# Expansion.net
KiCad netlist of a schematic drawn in Altium Designer
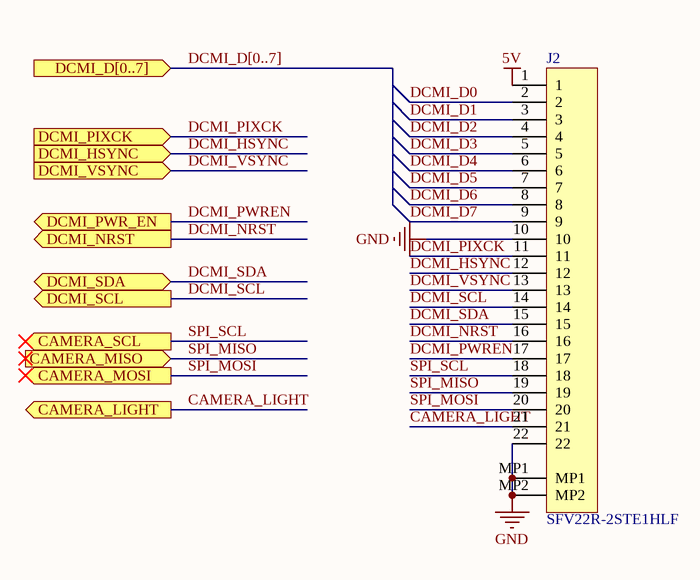
[diagram p0: Expansion.SchDoc]

(export (version "E")
  (design (tool "Eeschema 10.0.6"))
  (components
    (comp (ref "J2")
      (value "SFV22R-2STE1HLF")
      (footprint "fpc-22")
      (description "Connector")
      (fields (field (name "MANUFACTURER") "Amphenol FCI"))
      (libsource (lib "yildizIoT Library") (part "FPC-22"))
    )
  )
  (nets
    (net (code "1") (name "/CAMERA_LIGHT") (class "Default")
      (node (ref "J2") (pin "21") (pinfunction "21_21") (pintype "passive"))
    )
    (net (code "2") (name "/DCMI_D0") (class "Default")
      (node (ref "J2") (pin "2") (pinfunction "2_2") (pintype "passive"))
    )
    (net (code "3") (name "/DCMI_D1") (class "Default")
      (node (ref "J2") (pin "3") (pinfunction "3_3") (pintype "passive"))
    )
    (net (code "4") (name "/DCMI_D2") (class "Default")
      (node (ref "J2") (pin "4") (pinfunction "4_4") (pintype "passive"))
    )
    (net (code "5") (name "/DCMI_D3") (class "Default")
      (node (ref "J2") (pin "5") (pinfunction "5_5") (pintype "passive"))
    )
    (net (code "6") (name "/DCMI_D4") (class "Default")
      (node (ref "J2") (pin "6") (pinfunction "6_6") (pintype "passive"))
    )
    (net (code "7") (name "/DCMI_D5") (class "Default")
      (node (ref "J2") (pin "7") (pinfunction "7_7") (pintype "passive"))
    )
    (net (code "8") (name "/DCMI_D6") (class "Default")
      (node (ref "J2") (pin "8") (pinfunction "8_8") (pintype "passive"))
    )
    (net (code "9") (name "/DCMI_D7") (class "Default")
      (node (ref "J2") (pin "9") (pinfunction "9_9") (pintype "passive"))
    )
    (net (code "11") (name "/DCMI_HSYNC") (class "Default")
      (node (ref "J2") (pin "12") (pinfunction "12_12") (pintype "passive"))
    )
    (net (code "12") (name "/DCMI_NRST") (class "Default")
      (node (ref "J2") (pin "16") (pinfunction "16_16") (pintype "passive"))
    )
    (net (code "13") (name "/DCMI_PIXCK") (class "Default")
      (node (ref "J2") (pin "11") (pinfunction "11_11") (pintype "passive"))
    )
    (net (code "14") (name "/DCMI_PWREN") (class "Default")
      (node (ref "J2") (pin "17") (pinfunction "17_17") (pintype "passive"))
    )
    (net (code "15") (name "/DCMI_SCL") (class "Default")
      (node (ref "J2") (pin "14") (pinfunction "14_14") (pintype "passive"))
    )
    (net (code "16") (name "/DCMI_SDA") (class "Default")
      (node (ref "J2") (pin "15") (pinfunction "15_15") (pintype "passive"))
    )
    (net (code "17") (name "/DCMI_VSYNC") (class "Default")
      (node (ref "J2") (pin "13") (pinfunction "13_13") (pintype "passive"))
    )
    (net (code "18") (name "/SPI_MISO") (class "Default")
      (node (ref "J2") (pin "19") (pinfunction "19_19") (pintype "passive"))
    )
    (net (code "19") (name "/SPI_MOSI") (class "Default")
      (node (ref "J2") (pin "20") (pinfunction "20_20") (pintype "passive"))
    )
    (net (code "20") (name "/SPI_SCL") (class "Default")
      (node (ref "J2") (pin "18") (pinfunction "18_18") (pintype "passive"))
    )
    (net (code "21") (name "5V") (class "Default")
      (node (ref "J2") (pin "1") (pinfunction "1_1") (pintype "passive"))
    )
    (net (code "22") (name "GND") (class "Default")
      (node (ref "J2") (pin "10") (pinfunction "10_10") (pintype "passive"))
      (node (ref "J2") (pin "22") (pinfunction "22_22") (pintype "passive"))
      (node (ref "J2") (pin "MP1") (pinfunction "MP1_MP1") (pintype "passive"))
      (node (ref "J2") (pin "MP2") (pinfunction "MP2_MP2") (pintype "passive"))
    )
  )
)
